# 20250216.net
KiCad netlist of a schematic drawn in EasyEDA
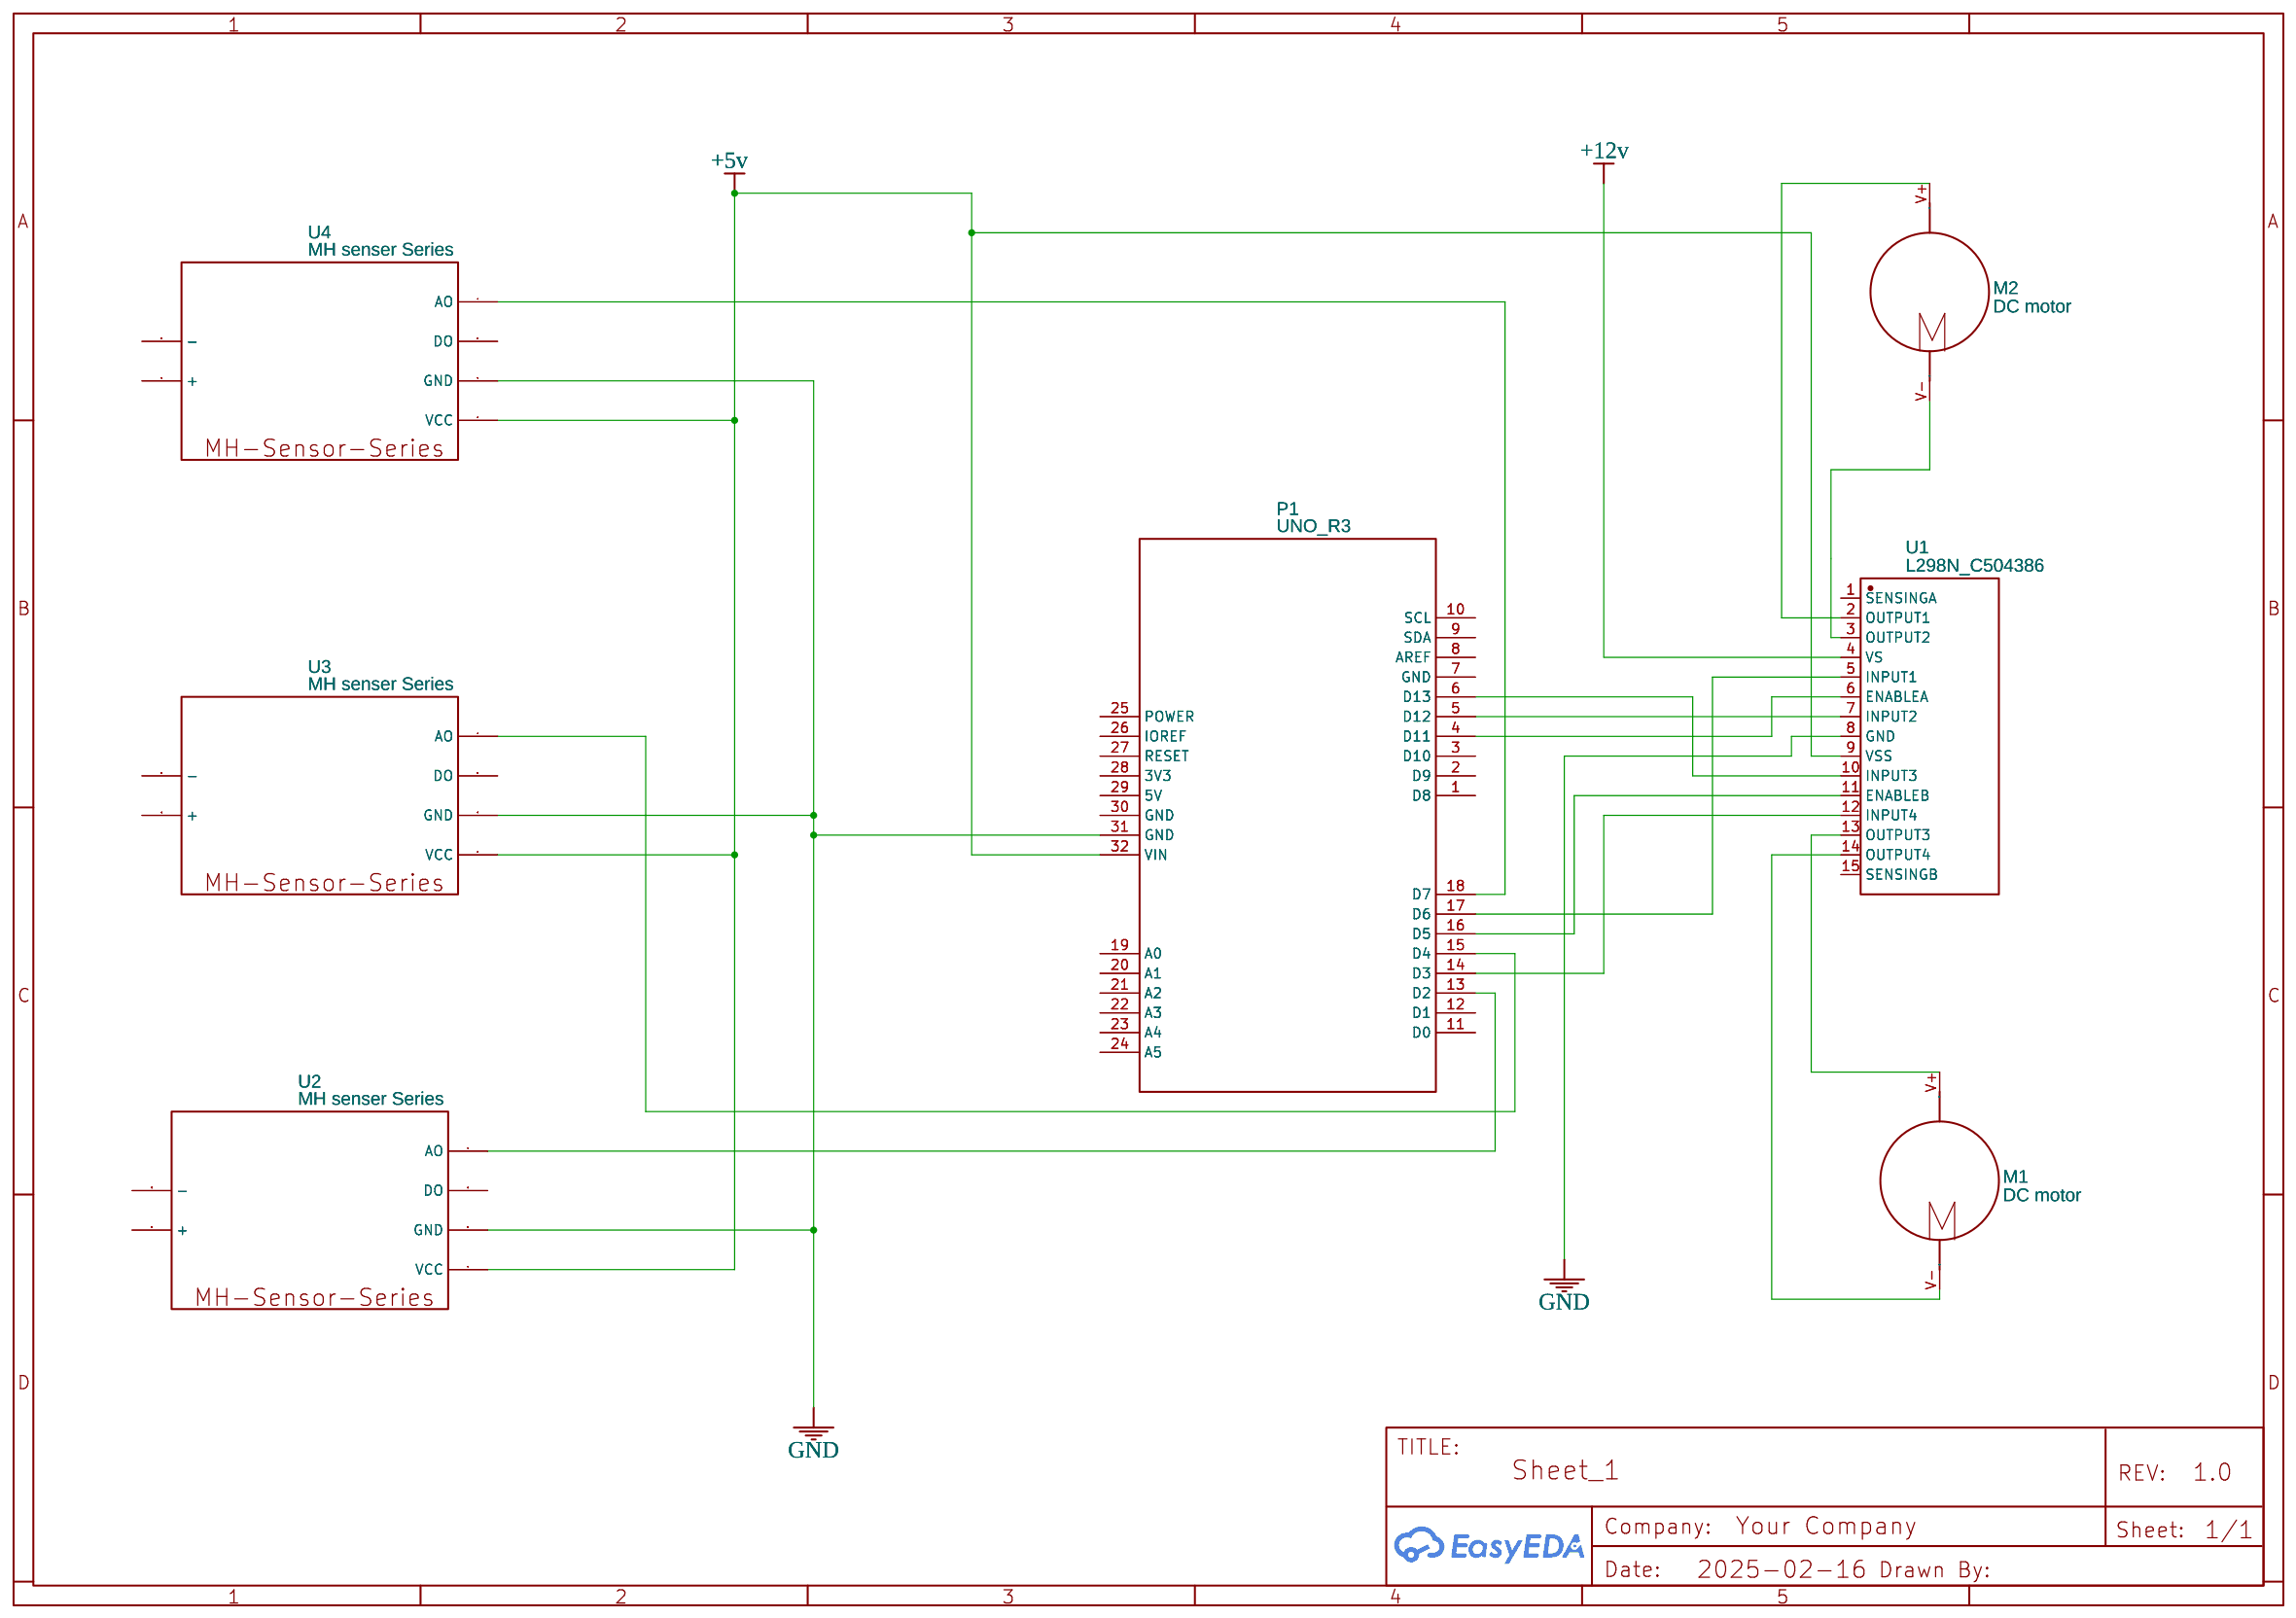
[diagram p0: schematic sheet]

(export (version "E")
  (design (tool "Eeschema 10.0.6"))
  (components
    (comp (ref "M1") (value "DC motor") (libsource (lib "") (part "DC motor")))
    (comp (ref "M2") (value "DC motor") (libsource (lib "") (part "DC motor")))
    (comp (ref "P1") (value "UNO_R3") (libsource (lib "") (part "UNO_R3")))
    (comp (ref "U1")
      (value "L298N_C504386")
      (fields (field (name "Manufacturer Part") "L298N") (field (name "Manufacturer") "Gcore(上海国芯)"))
      (libsource (lib "") (part "L298N_C504386"))
    )
    (comp (ref "U2") (value "MH senser Series") (libsource (lib "") (part "MH senser Series")))
    (comp (ref "U3") (value "MH senser Series") (libsource (lib "") (part "MH senser Series")))
    (comp (ref "U4") (value "MH senser Series") (libsource (lib "") (part "MH senser Series")))
  )
  (nets
    (net (code "1") (name "+5v") (class "Default")
      (node (ref "P1") (pin "32") (pinfunction "VIN_32") (pintype "unspecified"))
      (node (ref "U1") (pin "9") (pinfunction "VSS_9") (pintype "unspecified"))
      (node (ref "U2") (pin "1") (pinfunction "VCC_1") (pintype "unspecified"))
      (node (ref "U3") (pin "1") (pinfunction "VCC_1") (pintype "unspecified"))
      (node (ref "U4") (pin "1") (pinfunction "VCC_1") (pintype "unspecified"))
    )
    (net (code "2") (name "+12v") (class "Default")
      (node (ref "U1") (pin "4") (pinfunction "VS_4") (pintype "unspecified"))
    )
    (net (code "3") (name "GND") (class "Default")
      (node (ref "P1") (pin "31") (pinfunction "GND_31") (pintype "unspecified"))
      (node (ref "U1") (pin "8") (pinfunction "GND_8") (pintype "unspecified"))
      (node (ref "U2") (pin "2") (pinfunction "GND_2") (pintype "unspecified"))
      (node (ref "U3") (pin "2") (pinfunction "GND_2") (pintype "unspecified"))
      (node (ref "U4") (pin "2") (pinfunction "GND_2") (pintype "unspecified"))
    )
    (net (code "4") (name "Net-(M1-V1)") (class "Default")
      (node (ref "M1") (pin "V+") (pinfunction "V1_V+") (pintype "unspecified"))
      (node (ref "U1") (pin "13") (pinfunction "OUTPUT3_13") (pintype "unspecified"))
    )
    (net (code "5") (name "Net-(M1-V2)") (class "Default")
      (node (ref "M1") (pin "V-") (pinfunction "V2_V-") (pintype "unspecified"))
      (node (ref "U1") (pin "14") (pinfunction "OUTPUT4_14") (pintype "unspecified"))
    )
    (net (code "6") (name "Net-(M2-V1)") (class "Default")
      (node (ref "M2") (pin "V+") (pinfunction "V1_V+") (pintype "unspecified"))
      (node (ref "U1") (pin "2") (pinfunction "OUTPUT1_2") (pintype "unspecified"))
    )
    (net (code "7") (name "Net-(M2-V2)") (class "Default")
      (node (ref "M2") (pin "V-") (pinfunction "V2_V-") (pintype "unspecified"))
      (node (ref "U1") (pin "3") (pinfunction "OUTPUT2_3") (pintype "unspecified"))
    )
    (net (code "8") (name "Net-(P1-D2)") (class "Default")
      (node (ref "P1") (pin "13") (pinfunction "D2_13") (pintype "unspecified"))
      (node (ref "U2") (pin "4") (pinfunction "AO_4") (pintype "unspecified"))
    )
    (net (code "9") (name "Net-(P1-D3)") (class "Default")
      (node (ref "P1") (pin "14") (pinfunction "D3_14") (pintype "unspecified"))
      (node (ref "U1") (pin "12") (pinfunction "INPUT4_12") (pintype "unspecified"))
    )
    (net (code "10") (name "Net-(P1-D4)") (class "Default")
      (node (ref "P1") (pin "15") (pinfunction "D4_15") (pintype "unspecified"))
      (node (ref "U3") (pin "4") (pinfunction "AO_4") (pintype "unspecified"))
    )
    (net (code "11") (name "Net-(P1-D5)") (class "Default")
      (node (ref "P1") (pin "16") (pinfunction "D5_16") (pintype "unspecified"))
      (node (ref "U1") (pin "11") (pinfunction "ENABLEB_11") (pintype "unspecified"))
    )
    (net (code "12") (name "Net-(P1-D6)") (class "Default")
      (node (ref "P1") (pin "17") (pinfunction "D6_17") (pintype "unspecified"))
      (node (ref "U1") (pin "5") (pinfunction "INPUT1_5") (pintype "unspecified"))
    )
    (net (code "13") (name "Net-(P1-D7)") (class "Default")
      (node (ref "P1") (pin "18") (pinfunction "D7_18") (pintype "unspecified"))
      (node (ref "U4") (pin "4") (pinfunction "AO_4") (pintype "unspecified"))
    )
    (net (code "14") (name "Net-(P1-D11)") (class "Default")
      (node (ref "P1") (pin "4") (pinfunction "D11_4") (pintype "unspecified"))
      (node (ref "U1") (pin "6") (pinfunction "ENABLEA_6") (pintype "unspecified"))
    )
    (net (code "15") (name "Net-(P1-D12)") (class "Default")
      (node (ref "P1") (pin "5") (pinfunction "D12_5") (pintype "unspecified"))
      (node (ref "U1") (pin "7") (pinfunction "INPUT2_7") (pintype "unspecified"))
    )
    (net (code "16") (name "Net-(P1-D13)") (class "Default")
      (node (ref "P1") (pin "6") (pinfunction "D13_6") (pintype "unspecified"))
      (node (ref "U1") (pin "10") (pinfunction "INPUT3_10") (pintype "unspecified"))
    )
    (net (code "17") (name "unconnected-(P1-3V3-Pad28)") (class "Default")
      (node (ref "P1") (pin "28") (pinfunction "3V3_28") (pintype "unspecified"))
    )
    (net (code "18") (name "unconnected-(P1-5V-Pad29)") (class "Default")
      (node (ref "P1") (pin "29") (pinfunction "5V_29") (pintype "unspecified"))
    )
    (net (code "19") (name "unconnected-(P1-A0-Pad19)") (class "Default")
      (node (ref "P1") (pin "19") (pinfunction "A0_19") (pintype "unspecified"))
    )
    (net (code "20") (name "unconnected-(P1-A1-Pad20)") (class "Default")
      (node (ref "P1") (pin "20") (pinfunction "A1_20") (pintype "unspecified"))
    )
    (net (code "21") (name "unconnected-(P1-A2-Pad21)") (class "Default")
      (node (ref "P1") (pin "21") (pinfunction "A2_21") (pintype "unspecified"))
    )
    (net (code "22") (name "unconnected-(P1-A3-Pad22)") (class "Default")
      (node (ref "P1") (pin "22") (pinfunction "A3_22") (pintype "unspecified"))
    )
    (net (code "23") (name "unconnected-(P1-A4-Pad23)") (class "Default")
      (node (ref "P1") (pin "23") (pinfunction "A4_23") (pintype "unspecified"))
    )
    (net (code "24") (name "unconnected-(P1-A5-Pad24)") (class "Default")
      (node (ref "P1") (pin "24") (pinfunction "A5_24") (pintype "unspecified"))
    )
    (net (code "25") (name "unconnected-(P1-AREF-Pad8)") (class "Default")
      (node (ref "P1") (pin "8") (pinfunction "AREF_8") (pintype "unspecified"))
    )
    (net (code "26") (name "unconnected-(P1-D0-Pad11)") (class "Default")
      (node (ref "P1") (pin "11") (pinfunction "D0_11") (pintype "unspecified"))
    )
    (net (code "27") (name "unconnected-(P1-D1-Pad12)") (class "Default")
      (node (ref "P1") (pin "12") (pinfunction "D1_12") (pintype "unspecified"))
    )
    (net (code "28") (name "unconnected-(P1-D8-Pad1)") (class "Default")
      (node (ref "P1") (pin "1") (pinfunction "D8_1") (pintype "unspecified"))
    )
    (net (code "29") (name "unconnected-(P1-D9-Pad2)") (class "Default")
      (node (ref "P1") (pin "2") (pinfunction "D9_2") (pintype "unspecified"))
    )
    (net (code "30") (name "unconnected-(P1-D10-Pad3)") (class "Default")
      (node (ref "P1") (pin "3") (pinfunction "D10_3") (pintype "unspecified"))
    )
    (net (code "31") (name "unconnected-(P1-GND-Pad7)") (class "Default")
      (node (ref "P1") (pin "7") (pinfunction "GND_7") (pintype "unspecified"))
    )
    (net (code "32") (name "unconnected-(P1-GND-Pad30)") (class "Default")
      (node (ref "P1") (pin "30") (pinfunction "GND_30") (pintype "unspecified"))
    )
    (net (code "33") (name "unconnected-(P1-IOREF-Pad26)") (class "Default")
      (node (ref "P1") (pin "26") (pinfunction "IOREF_26") (pintype "unspecified"))
    )
    (net (code "34") (name "unconnected-(P1-POWER-Pad25)") (class "Default")
      (node (ref "P1") (pin "25") (pinfunction "POWER_25") (pintype "unspecified"))
    )
    (net (code "35") (name "unconnected-(P1-RESET-Pad27)") (class "Default")
      (node (ref "P1") (pin "27") (pinfunction "RESET_27") (pintype "unspecified"))
    )
    (net (code "36") (name "unconnected-(P1-SCL-Pad10)") (class "Default")
      (node (ref "P1") (pin "10") (pinfunction "SCL_10") (pintype "unspecified"))
    )
    (net (code "37") (name "unconnected-(P1-SDA-Pad9)") (class "Default")
      (node (ref "P1") (pin "9") (pinfunction "SDA_9") (pintype "unspecified"))
    )
    (net (code "38") (name "unconnected-(U1-SENSINGA-Pad1)") (class "Default")
      (node (ref "U1") (pin "1") (pinfunction "SENSINGA_1") (pintype "unspecified"))
    )
    (net (code "39") (name "unconnected-(U1-SENSINGB-Pad15)") (class "Default")
      (node (ref "U1") (pin "15") (pinfunction "SENSINGB_15") (pintype "unspecified"))
    )
    (net (code "40") (name "unconnected-(U2-+-Pad5)") (class "Default")
      (node (ref "U2") (pin "5") (pinfunction "+_5") (pintype "unspecified"))
    )
    (net (code "41") (name "unconnected-(U2---Pad6)") (class "Default")
      (node (ref "U2") (pin "6") (pinfunction "-_6") (pintype "unspecified"))
    )
    (net (code "42") (name "unconnected-(U2-DO-Pad3)") (class "Default")
      (node (ref "U2") (pin "3") (pinfunction "DO_3") (pintype "unspecified"))
    )
    (net (code "43") (name "unconnected-(U3-+-Pad5)") (class "Default")
      (node (ref "U3") (pin "5") (pinfunction "+_5") (pintype "unspecified"))
    )
    (net (code "44") (name "unconnected-(U3---Pad6)") (class "Default")
      (node (ref "U3") (pin "6") (pinfunction "-_6") (pintype "unspecified"))
    )
    (net (code "45") (name "unconnected-(U3-DO-Pad3)") (class "Default")
      (node (ref "U3") (pin "3") (pinfunction "DO_3") (pintype "unspecified"))
    )
    (net (code "46") (name "unconnected-(U4-+-Pad5)") (class "Default")
      (node (ref "U4") (pin "5") (pinfunction "+_5") (pintype "unspecified"))
    )
    (net (code "47") (name "unconnected-(U4---Pad6)") (class "Default")
      (node (ref "U4") (pin "6") (pinfunction "-_6") (pintype "unspecified"))
    )
    (net (code "48") (name "unconnected-(U4-DO-Pad3)") (class "Default")
      (node (ref "U4") (pin "3") (pinfunction "DO_3") (pintype "unspecified"))
    )
  )
)
